# CAN_Interface.net
KiCad netlist of a schematic drawn in EAGLE
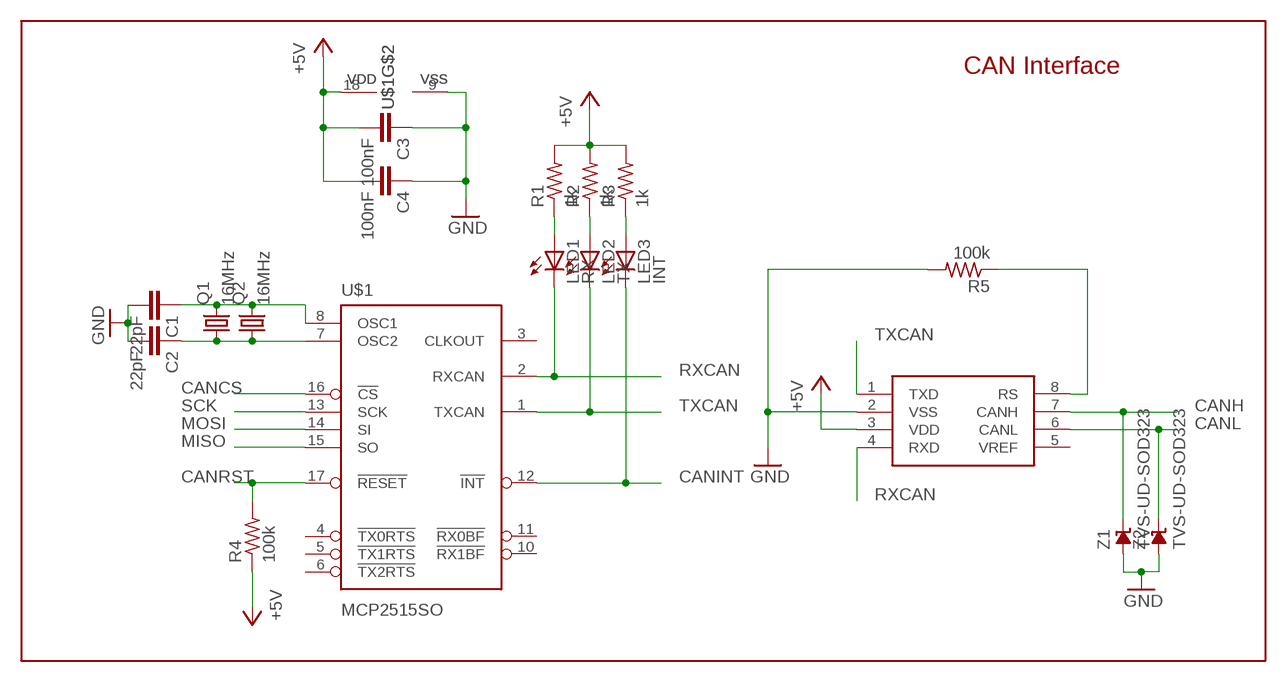
[diagram p0: schematic, sheet 1]

(export (version "E")
  (design (tool "Eeschema 10.0.6"))
  (components
    (comp (ref "C1")
      (value "22pF")
      (footprint "eagle-import:C0805K")
      (libsource (lib "eagle-import") (part "C-EUC0805K"))
    )
    (comp (ref "C2")
      (value "22pF")
      (footprint "eagle-import:C0805K")
      (libsource (lib "eagle-import") (part "C-EUC0805K"))
    )
    (comp (ref "C3")
      (value "100nF")
      (footprint "eagle-import:C0805K")
      (libsource (lib "eagle-import") (part "C-EUC0805K"))
    )
    (comp (ref "C4")
      (value "100nF")
      (footprint "eagle-import:C0805K")
      (libsource (lib "eagle-import") (part "C-EUC0805K"))
    )
    (comp (ref "LED1")
      (value "RX")
      (footprint "eagle-import:CHIP-LED0805")
      (libsource (lib "eagle-import") (part "LEDCHIP-LED0805"))
    )
    (comp (ref "LED2")
      (value "TX")
      (footprint "eagle-import:CHIP-LED0805")
      (libsource (lib "eagle-import") (part "LEDCHIP-LED0805"))
    )
    (comp (ref "LED3")
      (value "INT")
      (footprint "eagle-import:CHIP-LED0805")
      (libsource (lib "eagle-import") (part "LEDCHIP-LED0805"))
    )
    (comp (ref "Q1")
      (value "16MHz")
      (footprint "eagle-import:HC49_S")
      (libsource (lib "eagle-import") (part "CRYSTALHC49S"))
    )
    (comp (ref "Q2")
      (value "16MHz")
      (footprint "eagle-import:HC49UP")
      (libsource (lib "eagle-import") (part "CRYSTALHC49UP"))
    )
    (comp (ref "R1")
      (value "1k")
      (footprint "eagle-import:R0805")
      (libsource (lib "eagle-import") (part "R-US_R0805"))
    )
    (comp (ref "R2")
      (value "1k")
      (footprint "eagle-import:R0805")
      (libsource (lib "eagle-import") (part "R-US_R0805"))
    )
    (comp (ref "R3")
      (value "1k")
      (footprint "eagle-import:R0805")
      (libsource (lib "eagle-import") (part "R-US_R0805"))
    )
    (comp (ref "R4")
      (value "100k")
      (footprint "eagle-import:R0805")
      (libsource (lib "eagle-import") (part "R-US_R0805"))
    )
    (comp (ref "R5")
      (value "100k")
      (footprint "eagle-import:R0805")
      (libsource (lib "eagle-import") (part "R-US_R0805"))
    )
    (comp (ref "U$1")
      (value "MCP2515SO")
      (footprint "eagle-import:SO-18W")
      (libsource (lib "eagle-import") (part "MCP2515SO"))
    )
    (comp (ref "U1")
      (value "MCP2551")
      (footprint "eagle-import:SO08")
      (libsource (lib "eagle-import") (part "MCP2551"))
    )
    (comp (ref "Z1")
      (value "TVS-UD-SOD323")
      (footprint "eagle-import:SOD323")
      (libsource (lib "eagle-import") (part "TVS-UD-SOD323"))
    )
    (comp (ref "Z2")
      (value "TVS-UD-SOD323")
      (footprint "eagle-import:SOD323")
      (libsource (lib "eagle-import") (part "TVS-UD-SOD323"))
    )
  )
  (nets
    (net (code "1") (name "+5V") (class "Default")
      (node (ref "C3") (pin "2") (pinfunction "2_2") (pintype "passive"))
      (node (ref "C4") (pin "2") (pinfunction "2_2") (pintype "passive"))
      (node (ref "R1") (pin "2") (pinfunction "2_2") (pintype "passive"))
      (node (ref "R2") (pin "2") (pinfunction "2_2") (pintype "passive"))
      (node (ref "R3") (pin "2") (pinfunction "2_2") (pintype "passive"))
      (node (ref "R4") (pin "1") (pinfunction "1_1") (pintype "passive"))
      (node (ref "U$1") (pin "18") (pinfunction "VDD_18") (pintype "power_in"))
      (node (ref "U1") (pin "3") (pinfunction "VDD_3") (pintype "bidirectional"))
    )
    (net (code "2") (name "/CANCS") (class "Default")
      (node (ref "U$1") (pin "16") (pinfunction "~{CS}_16") (pintype "input"))
    )
    (net (code "3") (name "/CANH") (class "Default")
      (node (ref "U1") (pin "7") (pinfunction "CANH_7") (pintype "bidirectional"))
      (node (ref "Z1") (pin "C") (pinfunction "C_C") (pintype "passive"))
    )
    (net (code "4") (name "/CANINT") (class "Default")
      (node (ref "LED3") (pin "C") (pinfunction "C_C") (pintype "passive"))
      (node (ref "U$1") (pin "12") (pinfunction "~{INT}_12") (pintype "output"))
    )
    (net (code "5") (name "/CANL") (class "Default")
      (node (ref "U1") (pin "6") (pinfunction "CANL_6") (pintype "bidirectional"))
      (node (ref "Z2") (pin "C") (pinfunction "C_C") (pintype "passive"))
    )
    (net (code "6") (name "/CANRST") (class "Default")
      (node (ref "R4") (pin "2") (pinfunction "2_2") (pintype "passive"))
      (node (ref "U$1") (pin "17") (pinfunction "~{RESET}_17") (pintype "input"))
    )
    (net (code "7") (name "/MISO") (class "Default")
      (node (ref "U$1") (pin "15") (pinfunction "SO_15") (pintype "output"))
    )
    (net (code "8") (name "/MOSI") (class "Default")
      (node (ref "U$1") (pin "14") (pinfunction "SI_14") (pintype "input"))
    )
    (net (code "9") (name "/RXCAN") (class "Default")
      (node (ref "LED1") (pin "C") (pinfunction "C_C") (pintype "passive"))
      (node (ref "U$1") (pin "2") (pinfunction "RXCAN_2") (pintype "input"))
      (node (ref "U1") (pin "4") (pinfunction "RXD_4") (pintype "bidirectional"))
    )
    (net (code "10") (name "/SCK") (class "Default")
      (node (ref "U$1") (pin "13") (pinfunction "SCK_13") (pintype "input"))
    )
    (net (code "11") (name "/TXCAN") (class "Default")
      (node (ref "LED2") (pin "C") (pinfunction "C_C") (pintype "passive"))
      (node (ref "U$1") (pin "1") (pinfunction "TXCAN_1") (pintype "output"))
      (node (ref "U1") (pin "1") (pinfunction "TXD_1") (pintype "bidirectional"))
    )
    (net (code "12") (name "GND") (class "Default")
      (node (ref "C1") (pin "2") (pinfunction "2_2") (pintype "passive"))
      (node (ref "C2") (pin "2") (pinfunction "2_2") (pintype "passive"))
      (node (ref "C3") (pin "1") (pinfunction "1_1") (pintype "passive"))
      (node (ref "C4") (pin "1") (pinfunction "1_1") (pintype "passive"))
      (node (ref "R5") (pin "2") (pinfunction "2_2") (pintype "passive"))
      (node (ref "U$1") (pin "9") (pinfunction "VSS_9") (pintype "power_in"))
      (node (ref "U1") (pin "2") (pinfunction "VSS_2") (pintype "bidirectional"))
      (node (ref "Z1") (pin "A") (pinfunction "A_A") (pintype "passive"))
      (node (ref "Z2") (pin "A") (pinfunction "A_A") (pintype "passive"))
    )
    (net (code "13") (name "Net-(LED1-PadA)") (class "Default")
      (node (ref "LED1") (pin "A") (pinfunction "A_A") (pintype "passive"))
      (node (ref "R1") (pin "1") (pinfunction "1_1") (pintype "passive"))
    )
    (net (code "14") (name "Net-(LED2-PadA)") (class "Default")
      (node (ref "LED2") (pin "A") (pinfunction "A_A") (pintype "passive"))
      (node (ref "R2") (pin "1") (pinfunction "1_1") (pintype "passive"))
    )
    (net (code "15") (name "Net-(LED3-PadA)") (class "Default")
      (node (ref "LED3") (pin "A") (pinfunction "A_A") (pintype "passive"))
      (node (ref "R3") (pin "1") (pinfunction "1_1") (pintype "passive"))
    )
    (net (code "16") (name "Net-(U$1A-OSC1)") (class "Default")
      (node (ref "C1") (pin "1") (pinfunction "1_1") (pintype "passive"))
      (node (ref "Q1") (pin "2") (pinfunction "2_2") (pintype "passive"))
      (node (ref "Q2") (pin "2") (pinfunction "2_2") (pintype "passive"))
      (node (ref "U$1") (pin "8") (pinfunction "OSC1_8") (pintype "input"))
    )
    (net (code "17") (name "Net-(U$1A-OSC2)") (class "Default")
      (node (ref "C2") (pin "1") (pinfunction "1_1") (pintype "passive"))
      (node (ref "Q1") (pin "1") (pinfunction "1_1") (pintype "passive"))
      (node (ref "Q2") (pin "1") (pinfunction "1_1") (pintype "passive"))
      (node (ref "U$1") (pin "7") (pinfunction "OSC2_7") (pintype "output"))
    )
    (net (code "18") (name "Net-(U1-RS)") (class "Default")
      (node (ref "R5") (pin "1") (pinfunction "1_1") (pintype "passive"))
      (node (ref "U1") (pin "8") (pinfunction "RS_8") (pintype "bidirectional"))
    )
    (net (code "19") (name "unconnected-(U$1A-CLKOUT-Pad3)") (class "Default")
      (node (ref "U$1") (pin "3") (pinfunction "CLKOUT_3") (pintype "output"))
    )
    (net (code "20") (name "unconnected-(U$1A-~{RX0BF}-Pad11)") (class "Default")
      (node (ref "U$1") (pin "11") (pinfunction "~{RX0BF}_11") (pintype "output"))
    )
    (net (code "21") (name "unconnected-(U$1A-~{RX1BF}-Pad10)") (class "Default")
      (node (ref "U$1") (pin "10") (pinfunction "~{RX1BF}_10") (pintype "output"))
    )
    (net (code "22") (name "unconnected-(U$1A-~{TX0RTS}-Pad4)") (class "Default")
      (node (ref "U$1") (pin "4") (pinfunction "~{TX0RTS}_4") (pintype "input"))
    )
    (net (code "23") (name "unconnected-(U$1A-~{TX1RTS}-Pad5)") (class "Default")
      (node (ref "U$1") (pin "5") (pinfunction "~{TX1RTS}_5") (pintype "input"))
    )
    (net (code "24") (name "unconnected-(U$1A-~{TX2RTS}-Pad6)") (class "Default")
      (node (ref "U$1") (pin "6") (pinfunction "~{TX2RTS}_6") (pintype "input"))
    )
    (net (code "25") (name "unconnected-(U1-VREF-Pad5)") (class "Default")
      (node (ref "U1") (pin "5") (pinfunction "VREF_5") (pintype "bidirectional"))
    )
  )
)
